# CW312_K82_CardEdge.net
KiCad netlist of a schematic drawn in Altium Designer
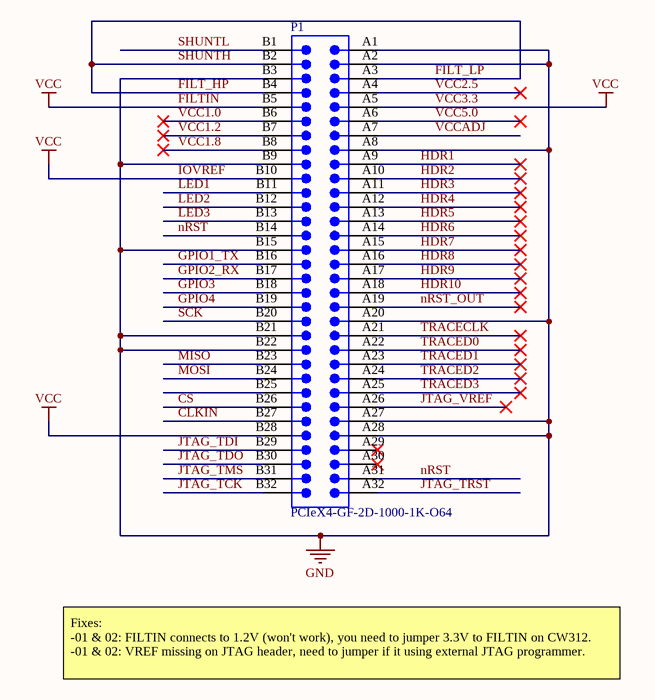
[diagram p0: CW312_K82_CardEdge.SchDoc]

(export (version "E")
  (design (tool "Eeschema 10.0.6"))
  (components
    (comp (ref "P1")
      (value "PCIeX4-GF-2D-1000-1K-O64")
      (footprint "PCIeX4-GF-2D-1000-1K-O64")
      (description "Golden finger, PCIeX4, Dual, Opposite, Pitch 1mm, 64-Position")
      (fields (field (name "PUBLISHER") "Altium"))
      (libsource (lib "Altium Content Vault") (part "PCIeX4-GF-2D-1000-1K-O64"))
    )
  )
  (nets
    (net (code "1") (name "/CLKIN") (class "Default")
      (node (ref "P1") (pin "B27") (pinfunction "B27_B27") (pintype "passive"))
    )
    (net (code "2") (name "/CS") (class "Default")
      (node (ref "P1") (pin "B26") (pinfunction "B26_B26") (pintype "passive"))
    )
    (net (code "3") (name "/FILT_HP") (class "Default")
      (node (ref "P1") (pin "A3") (pinfunction "A3_A3") (pintype "passive"))
      (node (ref "P1") (pin "B2") (pinfunction "B2_B2") (pintype "passive"))
      (node (ref "P1") (pin "B4") (pinfunction "B4_B4") (pintype "passive"))
    )
    (net (code "4") (name "/GPIO1_TX") (class "Default")
      (node (ref "P1") (pin "B16") (pinfunction "B16_B16") (pintype "passive"))
    )
    (net (code "5") (name "/GPIO2_RX") (class "Default")
      (node (ref "P1") (pin "B17") (pinfunction "B17_B17") (pintype "passive"))
    )
    (net (code "6") (name "/GPIO3") (class "Default")
      (node (ref "P1") (pin "B18") (pinfunction "B18_B18") (pintype "passive"))
    )
    (net (code "7") (name "/GPIO4") (class "Default")
      (node (ref "P1") (pin "B19") (pinfunction "B19_B19") (pintype "passive"))
    )
    (net (code "8") (name "/HDR1") (class "Default")
      (node (ref "P1") (pin "A9") (pinfunction "A9_A9") (pintype "passive+no_connect"))
    )
    (net (code "9") (name "/HDR2") (class "Default")
      (node (ref "P1") (pin "A10") (pinfunction "A10_A10") (pintype "passive+no_connect"))
    )
    (net (code "10") (name "/HDR3") (class "Default")
      (node (ref "P1") (pin "A11") (pinfunction "A11_A11") (pintype "passive+no_connect"))
    )
    (net (code "11") (name "/HDR4") (class "Default")
      (node (ref "P1") (pin "A12") (pinfunction "A12_A12") (pintype "passive+no_connect"))
    )
    (net (code "12") (name "/HDR5") (class "Default")
      (node (ref "P1") (pin "A13") (pinfunction "A13_A13") (pintype "passive+no_connect"))
    )
    (net (code "13") (name "/HDR6") (class "Default")
      (node (ref "P1") (pin "A14") (pinfunction "A14_A14") (pintype "passive+no_connect"))
    )
    (net (code "14") (name "/HDR7") (class "Default")
      (node (ref "P1") (pin "A15") (pinfunction "A15_A15") (pintype "passive+no_connect"))
    )
    (net (code "15") (name "/HDR8") (class "Default")
      (node (ref "P1") (pin "A16") (pinfunction "A16_A16") (pintype "passive+no_connect"))
    )
    (net (code "16") (name "/HDR9") (class "Default")
      (node (ref "P1") (pin "A17") (pinfunction "A17_A17") (pintype "passive+no_connect"))
    )
    (net (code "17") (name "/HDR10") (class "Default")
      (node (ref "P1") (pin "A18") (pinfunction "A18_A18") (pintype "passive+no_connect"))
    )
    (net (code "18") (name "/JTAG_TCK") (class "Default")
      (node (ref "P1") (pin "B32") (pinfunction "B32_B32") (pintype "passive"))
    )
    (net (code "19") (name "/JTAG_TDI") (class "Default")
      (node (ref "P1") (pin "B29") (pinfunction "B29_B29") (pintype "passive"))
    )
    (net (code "20") (name "/JTAG_TDO") (class "Default")
      (node (ref "P1") (pin "B30") (pinfunction "B30_B30") (pintype "passive"))
    )
    (net (code "21") (name "/JTAG_TMS") (class "Default")
      (node (ref "P1") (pin "B31") (pinfunction "B31_B31") (pintype "passive"))
    )
    (net (code "22") (name "/JTAG_TRST") (class "Default")
      (node (ref "P1") (pin "A32") (pinfunction "A32_A32") (pintype "passive"))
    )
    (net (code "23") (name "/JTAG_VREF") (class "Default")
      (node (ref "P1") (pin "A26") (pinfunction "A26_A26") (pintype "passive+no_connect"))
    )
    (net (code "24") (name "/LED1") (class "Default")
      (node (ref "P1") (pin "B11") (pinfunction "B11_B11") (pintype "passive"))
    )
    (net (code "25") (name "/LED2") (class "Default")
      (node (ref "P1") (pin "B12") (pinfunction "B12_B12") (pintype "passive"))
    )
    (net (code "26") (name "/LED3") (class "Default")
      (node (ref "P1") (pin "B13") (pinfunction "B13_B13") (pintype "passive"))
    )
    (net (code "27") (name "/MISO") (class "Default")
      (node (ref "P1") (pin "B23") (pinfunction "B23_B23") (pintype "passive"))
    )
    (net (code "28") (name "/MOSI") (class "Default")
      (node (ref "P1") (pin "B24") (pinfunction "B24_B24") (pintype "passive"))
    )
    (net (code "29") (name "/SCK") (class "Default")
      (node (ref "P1") (pin "B20") (pinfunction "B20_B20") (pintype "passive"))
    )
    (net (code "30") (name "/SHUNTL") (class "Default")
      (node (ref "P1") (pin "B1") (pinfunction "B1_B1") (pintype "passive"))
    )
    (net (code "31") (name "/TRACECLK") (class "Default")
      (node (ref "P1") (pin "A21") (pinfunction "A21_A21") (pintype "passive+no_connect"))
    )
    (net (code "32") (name "/TRACED0") (class "Default")
      (node (ref "P1") (pin "A22") (pinfunction "A22_A22") (pintype "passive+no_connect"))
    )
    (net (code "33") (name "/TRACED1") (class "Default")
      (node (ref "P1") (pin "A23") (pinfunction "A23_A23") (pintype "passive+no_connect"))
    )
    (net (code "34") (name "/TRACED2") (class "Default")
      (node (ref "P1") (pin "A24") (pinfunction "A24_A24") (pintype "passive+no_connect"))
    )
    (net (code "35") (name "/TRACED3") (class "Default")
      (node (ref "P1") (pin "A25") (pinfunction "A25_A25") (pintype "passive+no_connect"))
    )
    (net (code "36") (name "/VCC1.0") (class "Default")
      (node (ref "P1") (pin "B6") (pinfunction "B6_B6") (pintype "passive+no_connect"))
    )
    (net (code "37") (name "/VCC1.2") (class "Default")
      (node (ref "P1") (pin "B7") (pinfunction "B7_B7") (pintype "passive+no_connect"))
    )
    (net (code "38") (name "/VCC1.8") (class "Default")
      (node (ref "P1") (pin "B8") (pinfunction "B8_B8") (pintype "passive+no_connect"))
    )
    (net (code "39") (name "/VCC2.5") (class "Default")
      (node (ref "P1") (pin "A4") (pinfunction "A4_A4") (pintype "passive+no_connect"))
    )
    (net (code "40") (name "/VCC5.0") (class "Default")
      (node (ref "P1") (pin "A6") (pinfunction "A6_A6") (pintype "passive+no_connect"))
    )
    (net (code "41") (name "/VCCADJ") (class "Default")
      (node (ref "P1") (pin "A7") (pinfunction "A7_A7") (pintype "passive"))
    )
    (net (code "42") (name "/nRST") (class "Default")
      (node (ref "P1") (pin "A31") (pinfunction "A31_A31") (pintype "passive"))
      (node (ref "P1") (pin "B14") (pinfunction "B14_B14") (pintype "passive"))
    )
    (net (code "43") (name "/nRST_OUT") (class "Default")
      (node (ref "P1") (pin "A19") (pinfunction "A19_A19") (pintype "passive+no_connect"))
    )
    (net (code "44") (name "GND") (class "Default")
      (node (ref "P1") (pin "A1") (pinfunction "A1_A1") (pintype "passive"))
      (node (ref "P1") (pin "A2") (pinfunction "A2_A2") (pintype "passive"))
      (node (ref "P1") (pin "A20") (pinfunction "A20_A20") (pintype "passive"))
      (node (ref "P1") (pin "A27") (pinfunction "A27_A27") (pintype "passive"))
      (node (ref "P1") (pin "A28") (pinfunction "A28_A28") (pintype "passive"))
      (node (ref "P1") (pin "A8") (pinfunction "A8_A8") (pintype "passive"))
      (node (ref "P1") (pin "B15") (pinfunction "B15_B15") (pintype "passive"))
      (node (ref "P1") (pin "B21") (pinfunction "B21_B21") (pintype "passive"))
      (node (ref "P1") (pin "B22") (pinfunction "B22_B22") (pintype "passive"))
      (node (ref "P1") (pin "B3") (pinfunction "B3_B3") (pintype "passive"))
      (node (ref "P1") (pin "B9") (pinfunction "B9_B9") (pintype "passive"))
    )
    (net (code "45") (name "VCC") (class "Default")
      (node (ref "P1") (pin "A5") (pinfunction "A5_A5") (pintype "passive"))
      (node (ref "P1") (pin "B10") (pinfunction "B10_B10") (pintype "passive"))
      (node (ref "P1") (pin "B28") (pinfunction "B28_B28") (pintype "passive"))
      (node (ref "P1") (pin "B5") (pinfunction "B5_B5") (pintype "passive"))
    )
    (net (code "46") (name "unconnected-(P1-PadA29)") (class "Default")
      (node (ref "P1") (pin "A29") (pinfunction "A29_A29") (pintype "passive+no_connect"))
    )
    (net (code "47") (name "unconnected-(P1-PadA30)") (class "Default")
      (node (ref "P1") (pin "A30") (pinfunction "A30_A30") (pintype "passive+no_connect"))
    )
    (net (code "48") (name "unconnected-(P1-PadB25)") (class "Default")
      (node (ref "P1") (pin "B25") (pinfunction "B25_B25") (pintype "passive"))
    )
  )
)
